# connectors.net
KiCad netlist of a schematic drawn in Altium Designer
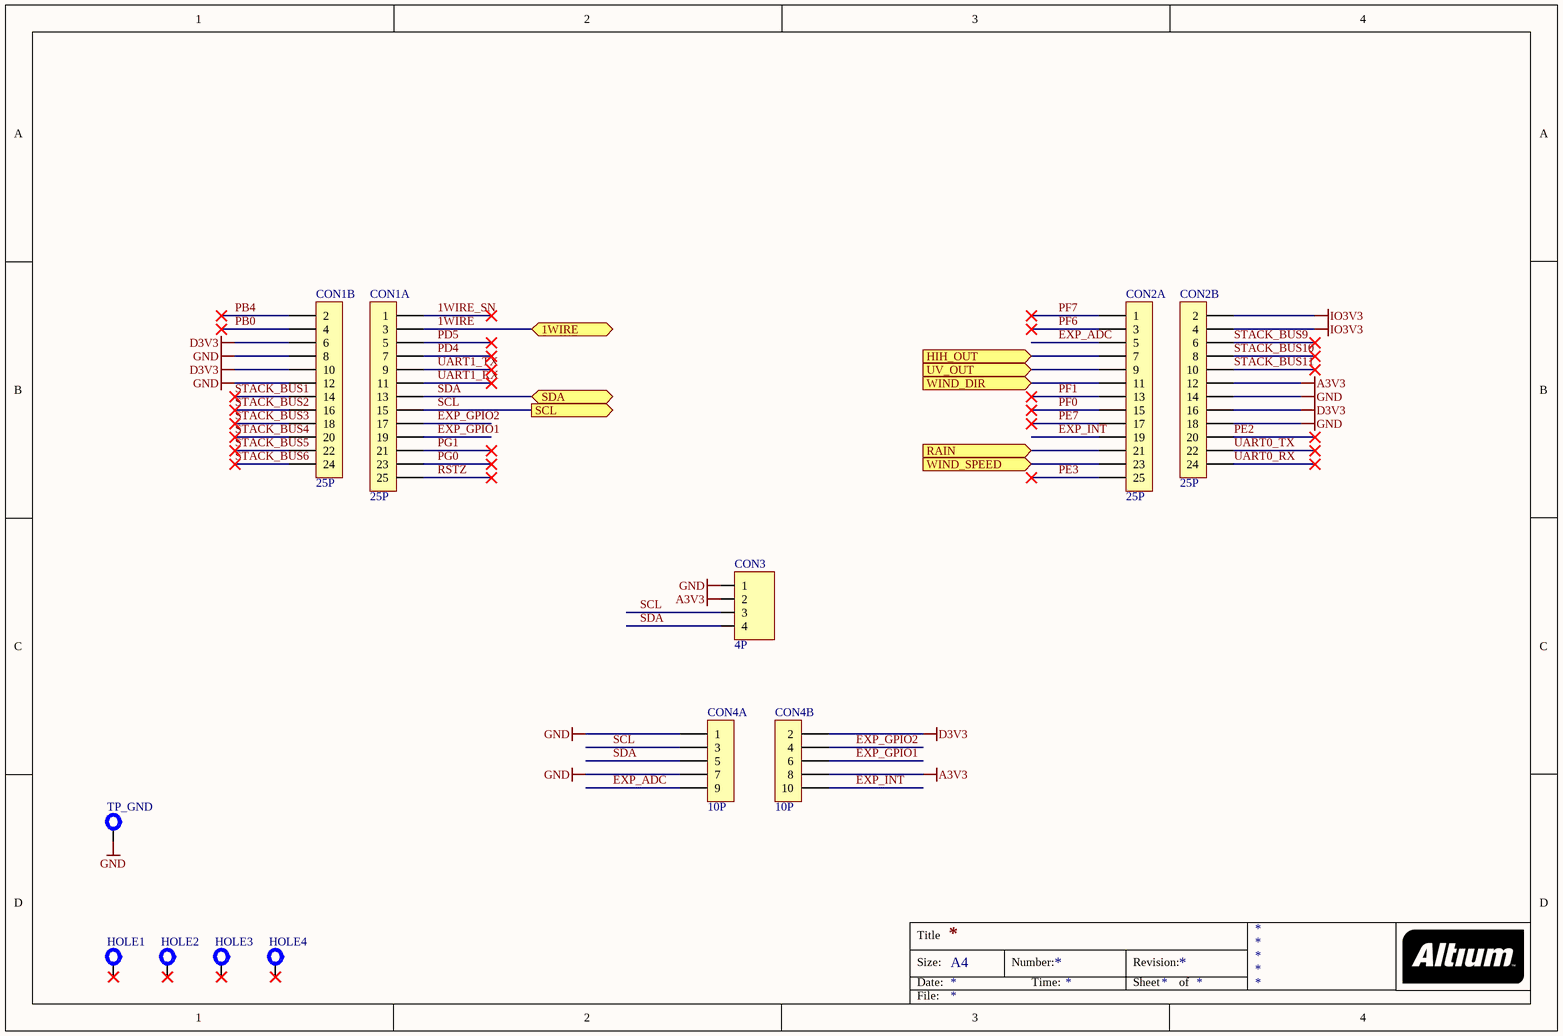
[diagram p0: connectors.SchDoc]

(export (version "E")
  (design (tool "Eeschema 10.0.6"))
  (components
    (comp (ref "CON1")
      (value "25P")
      (footprint "DF9-25-STACK")
      (description "Connector 25 Pins")
      (fields (field (name "OWNER") "Ricardo Rodrigues"))
      (libsource (lib "") (part "CON25_1"))
    )
    (comp (ref "CON2")
      (value "25P")
      (footprint "DF9-25-STACK")
      (description "Connector 25 Pins")
      (fields (field (name "OWNER") "Ricardo Rodrigues"))
      (libsource (lib "") (part "CON25_1"))
    )
    (comp (ref "CON3")
      (value "4P")
      (footprint "SIP-4")
      (description "Connector 4 pins")
      (fields (field (name "OWNER") "Rui Rebelo"))
      (libsource (lib "Alcetronics_EM") (part "CON04"))
    )
    (comp (ref "CON4")
      (value "10P")
      (footprint "IDC-10")
      (description "Connector 10 Pins")
      (fields (field (name "OWNER") "António Silva"))
      (libsource (lib "") (part "CON10_1"))
    )
    (comp (ref "HOLE1")
      (value "HOLE")
      (footprint "NPTH-3MM")
      (description "PCB Fixation Hole M3")
      (fields (field (name "OWNER") "Nuno Brum"))
      (libsource (lib "Alcetronics_EM") (part "PCB HOLE"))
    )
    (comp (ref "HOLE2")
      (value "HOLE")
      (footprint "NPTH-3MM")
      (description "PCB Fixation Hole M3")
      (fields (field (name "OWNER") "Nuno Brum"))
      (libsource (lib "Alcetronics_EM") (part "PCB HOLE"))
    )
    (comp (ref "HOLE3")
      (value "HOLE")
      (footprint "NPTH-3MM")
      (description "PCB Fixation Hole M3")
      (fields (field (name "OWNER") "Nuno Brum"))
      (libsource (lib "Alcetronics_EM") (part "PCB HOLE"))
    )
    (comp (ref "HOLE4")
      (value "HOLE")
      (footprint "NPTH-3MM")
      (description "PCB Fixation Hole M3")
      (fields (field (name "OWNER") "Nuno Brum"))
      (libsource (lib "Alcetronics_EM") (part "PCB HOLE"))
    )
    (comp (ref "TP_GND")
      (value "Test Point")
      (footprint "TEST-PROBE2")
      (description "Test/Probe Point")
      (fields (field (name "OWNER") "Nuno Brum"))
      (libsource (lib "Alcetronics_EM") (part "TEST-PROBE"))
    )
  )
  (nets
    (net (code "1") (name "/1WIRE") (class "Default")
      (node (ref "CON1") (pin "3") (pinfunction "3_3") (pintype "passive"))
    )
    (net (code "2") (name "/1WIRE_SN") (class "Default")
      (node (ref "CON1") (pin "1") (pinfunction "1_1") (pintype "passive+no_connect"))
    )
    (net (code "3") (name "/EXP_ADC") (class "Default")
      (node (ref "CON2") (pin "5") (pinfunction "5_5") (pintype "passive"))
      (node (ref "CON4") (pin "9") (pinfunction "9_9") (pintype "passive"))
    )
    (net (code "4") (name "/EXP_GPIO1") (class "Default")
      (node (ref "CON1") (pin "19") (pinfunction "19_19") (pintype "passive"))
      (node (ref "CON4") (pin "6") (pinfunction "6_6") (pintype "passive"))
    )
    (net (code "5") (name "/EXP_GPIO2") (class "Default")
      (node (ref "CON1") (pin "17") (pinfunction "17_17") (pintype "passive"))
      (node (ref "CON4") (pin "4") (pinfunction "4_4") (pintype "passive"))
    )
    (net (code "6") (name "/EXP_INT") (class "Default")
      (node (ref "CON2") (pin "19") (pinfunction "19_19") (pintype "passive"))
      (node (ref "CON4") (pin "10") (pinfunction "10_10") (pintype "passive"))
    )
    (net (code "7") (name "/HIH_OUT") (class "Default")
      (node (ref "CON2") (pin "7") (pinfunction "7_7") (pintype "passive"))
    )
    (net (code "8") (name "/PB0") (class "Default")
      (node (ref "CON1") (pin "4") (pinfunction "4_4") (pintype "passive+no_connect"))
    )
    (net (code "9") (name "/PB4") (class "Default")
      (node (ref "CON1") (pin "2") (pinfunction "2_2") (pintype "passive+no_connect"))
    )
    (net (code "10") (name "/PD4") (class "Default")
      (node (ref "CON1") (pin "7") (pinfunction "7_7") (pintype "passive+no_connect"))
    )
    (net (code "11") (name "/PD5") (class "Default")
      (node (ref "CON1") (pin "5") (pinfunction "5_5") (pintype "passive+no_connect"))
    )
    (net (code "12") (name "/PE2") (class "Default")
      (node (ref "CON2") (pin "20") (pinfunction "20_20") (pintype "passive+no_connect"))
    )
    (net (code "13") (name "/PE3") (class "Default")
      (node (ref "CON2") (pin "25") (pinfunction "25_25") (pintype "passive+no_connect"))
    )
    (net (code "14") (name "/PE7") (class "Default")
      (node (ref "CON2") (pin "17") (pinfunction "17_17") (pintype "passive+no_connect"))
    )
    (net (code "15") (name "/PF0") (class "Default")
      (node (ref "CON2") (pin "15") (pinfunction "15_15") (pintype "passive+no_connect"))
    )
    (net (code "16") (name "/PF1") (class "Default")
      (node (ref "CON2") (pin "13") (pinfunction "13_13") (pintype "passive+no_connect"))
    )
    (net (code "17") (name "/PF6") (class "Default")
      (node (ref "CON2") (pin "3") (pinfunction "3_3") (pintype "passive+no_connect"))
    )
    (net (code "18") (name "/PF7") (class "Default")
      (node (ref "CON2") (pin "1") (pinfunction "1_1") (pintype "passive+no_connect"))
    )
    (net (code "19") (name "/PG0") (class "Default")
      (node (ref "CON1") (pin "23") (pinfunction "23_23") (pintype "passive+no_connect"))
    )
    (net (code "20") (name "/PG1") (class "Default")
      (node (ref "CON1") (pin "21") (pinfunction "21_21") (pintype "passive+no_connect"))
    )
    (net (code "21") (name "/RAIN") (class "Default")
      (node (ref "CON2") (pin "21") (pinfunction "21_21") (pintype "passive"))
    )
    (net (code "22") (name "/RSTZ") (class "Default")
      (node (ref "CON1") (pin "25") (pinfunction "25_25") (pintype "passive+no_connect"))
    )
    (net (code "23") (name "/SCL") (class "Default")
      (node (ref "CON1") (pin "15") (pinfunction "15_15") (pintype "passive"))
      (node (ref "CON3") (pin "3") (pinfunction "3_3") (pintype "passive"))
      (node (ref "CON4") (pin "3") (pinfunction "3_3") (pintype "passive"))
    )
    (net (code "24") (name "/SDA") (class "Default")
      (node (ref "CON1") (pin "13") (pinfunction "13_13") (pintype "passive"))
      (node (ref "CON3") (pin "4") (pinfunction "4_4") (pintype "passive"))
      (node (ref "CON4") (pin "5") (pinfunction "5_5") (pintype "passive"))
    )
    (net (code "25") (name "/STACK_BUS1") (class "Default")
      (node (ref "CON1") (pin "14") (pinfunction "14_14") (pintype "passive+no_connect"))
    )
    (net (code "26") (name "/STACK_BUS2") (class "Default")
      (node (ref "CON1") (pin "16") (pinfunction "16_16") (pintype "passive+no_connect"))
    )
    (net (code "27") (name "/STACK_BUS3") (class "Default")
      (node (ref "CON1") (pin "18") (pinfunction "18_18") (pintype "passive+no_connect"))
    )
    (net (code "28") (name "/STACK_BUS4") (class "Default")
      (node (ref "CON1") (pin "20") (pinfunction "20_20") (pintype "passive+no_connect"))
    )
    (net (code "29") (name "/STACK_BUS5") (class "Default")
      (node (ref "CON1") (pin "22") (pinfunction "22_22") (pintype "passive+no_connect"))
    )
    (net (code "30") (name "/STACK_BUS6") (class "Default")
      (node (ref "CON1") (pin "24") (pinfunction "24_24") (pintype "passive+no_connect"))
    )
    (net (code "31") (name "/STACK_BUS9") (class "Default")
      (node (ref "CON2") (pin "6") (pinfunction "6_6") (pintype "passive+no_connect"))
    )
    (net (code "32") (name "/STACK_BUS10") (class "Default")
      (node (ref "CON2") (pin "8") (pinfunction "8_8") (pintype "passive+no_connect"))
    )
    (net (code "33") (name "/STACK_BUS11") (class "Default")
      (node (ref "CON2") (pin "10") (pinfunction "10_10") (pintype "passive+no_connect"))
    )
    (net (code "34") (name "/UART0_RX") (class "Default")
      (node (ref "CON2") (pin "24") (pinfunction "24_24") (pintype "passive+no_connect"))
    )
    (net (code "35") (name "/UART0_TX") (class "Default")
      (node (ref "CON2") (pin "22") (pinfunction "22_22") (pintype "passive+no_connect"))
    )
    (net (code "36") (name "/UART1_RX") (class "Default")
      (node (ref "CON1") (pin "11") (pinfunction "11_11") (pintype "passive+no_connect"))
    )
    (net (code "37") (name "/UART1_TX") (class "Default")
      (node (ref "CON1") (pin "9") (pinfunction "9_9") (pintype "passive+no_connect"))
    )
    (net (code "38") (name "/UV_OUT") (class "Default")
      (node (ref "CON2") (pin "9") (pinfunction "9_9") (pintype "passive"))
    )
    (net (code "39") (name "/WIND_DIR") (class "Default")
      (node (ref "CON2") (pin "11") (pinfunction "11_11") (pintype "passive"))
    )
    (net (code "40") (name "/WIND_SPEED") (class "Default")
      (node (ref "CON2") (pin "23") (pinfunction "23_23") (pintype "passive"))
    )
    (net (code "41") (name "A3V3") (class "Default")
      (node (ref "CON2") (pin "12") (pinfunction "12_12") (pintype "passive"))
      (node (ref "CON3") (pin "2") (pinfunction "2_2") (pintype "passive"))
      (node (ref "CON4") (pin "8") (pinfunction "8_8") (pintype "passive"))
    )
    (net (code "42") (name "D3V3") (class "Default")
      (node (ref "CON1") (pin "10") (pinfunction "10_10") (pintype "passive"))
      (node (ref "CON1") (pin "6") (pinfunction "6_6") (pintype "passive"))
      (node (ref "CON2") (pin "16") (pinfunction "16_16") (pintype "passive"))
      (node (ref "CON4") (pin "2") (pinfunction "2_2") (pintype "passive"))
    )
    (net (code "43") (name "GND") (class "Default")
      (node (ref "CON1") (pin "12") (pinfunction "12_12") (pintype "passive"))
      (node (ref "CON1") (pin "8") (pinfunction "8_8") (pintype "passive"))
      (node (ref "CON2") (pin "14") (pinfunction "14_14") (pintype "passive"))
      (node (ref "CON2") (pin "18") (pinfunction "18_18") (pintype "passive"))
      (node (ref "CON3") (pin "1") (pinfunction "1_1") (pintype "passive"))
      (node (ref "CON4") (pin "1") (pinfunction "1_1") (pintype "passive"))
      (node (ref "CON4") (pin "7") (pinfunction "7_7") (pintype "passive"))
      (node (ref "TP_GND") (pin "1") (pinfunction "TP_1") (pintype "passive"))
    )
    (net (code "44") (name "IO3V3") (class "Default")
      (node (ref "CON2") (pin "2") (pinfunction "2_2") (pintype "passive"))
      (node (ref "CON2") (pin "4") (pinfunction "4_4") (pintype "passive"))
    )
    (net (code "45") (name "unconnected-(HOLE1-TP-Pad1)") (class "Default")
      (node (ref "HOLE1") (pin "1") (pinfunction "TP_1") (pintype "passive+no_connect"))
    )
    (net (code "46") (name "unconnected-(HOLE2-TP-Pad1)") (class "Default")
      (node (ref "HOLE2") (pin "1") (pinfunction "TP_1") (pintype "passive+no_connect"))
    )
    (net (code "47") (name "unconnected-(HOLE3-TP-Pad1)") (class "Default")
      (node (ref "HOLE3") (pin "1") (pinfunction "TP_1") (pintype "passive+no_connect"))
    )
    (net (code "48") (name "unconnected-(HOLE4-TP-Pad1)") (class "Default")
      (node (ref "HOLE4") (pin "1") (pinfunction "TP_1") (pintype "passive+no_connect"))
    )
  )
)
